# slimwatch_rev01.net
KiCad netlist of a schematic drawn in EAGLE
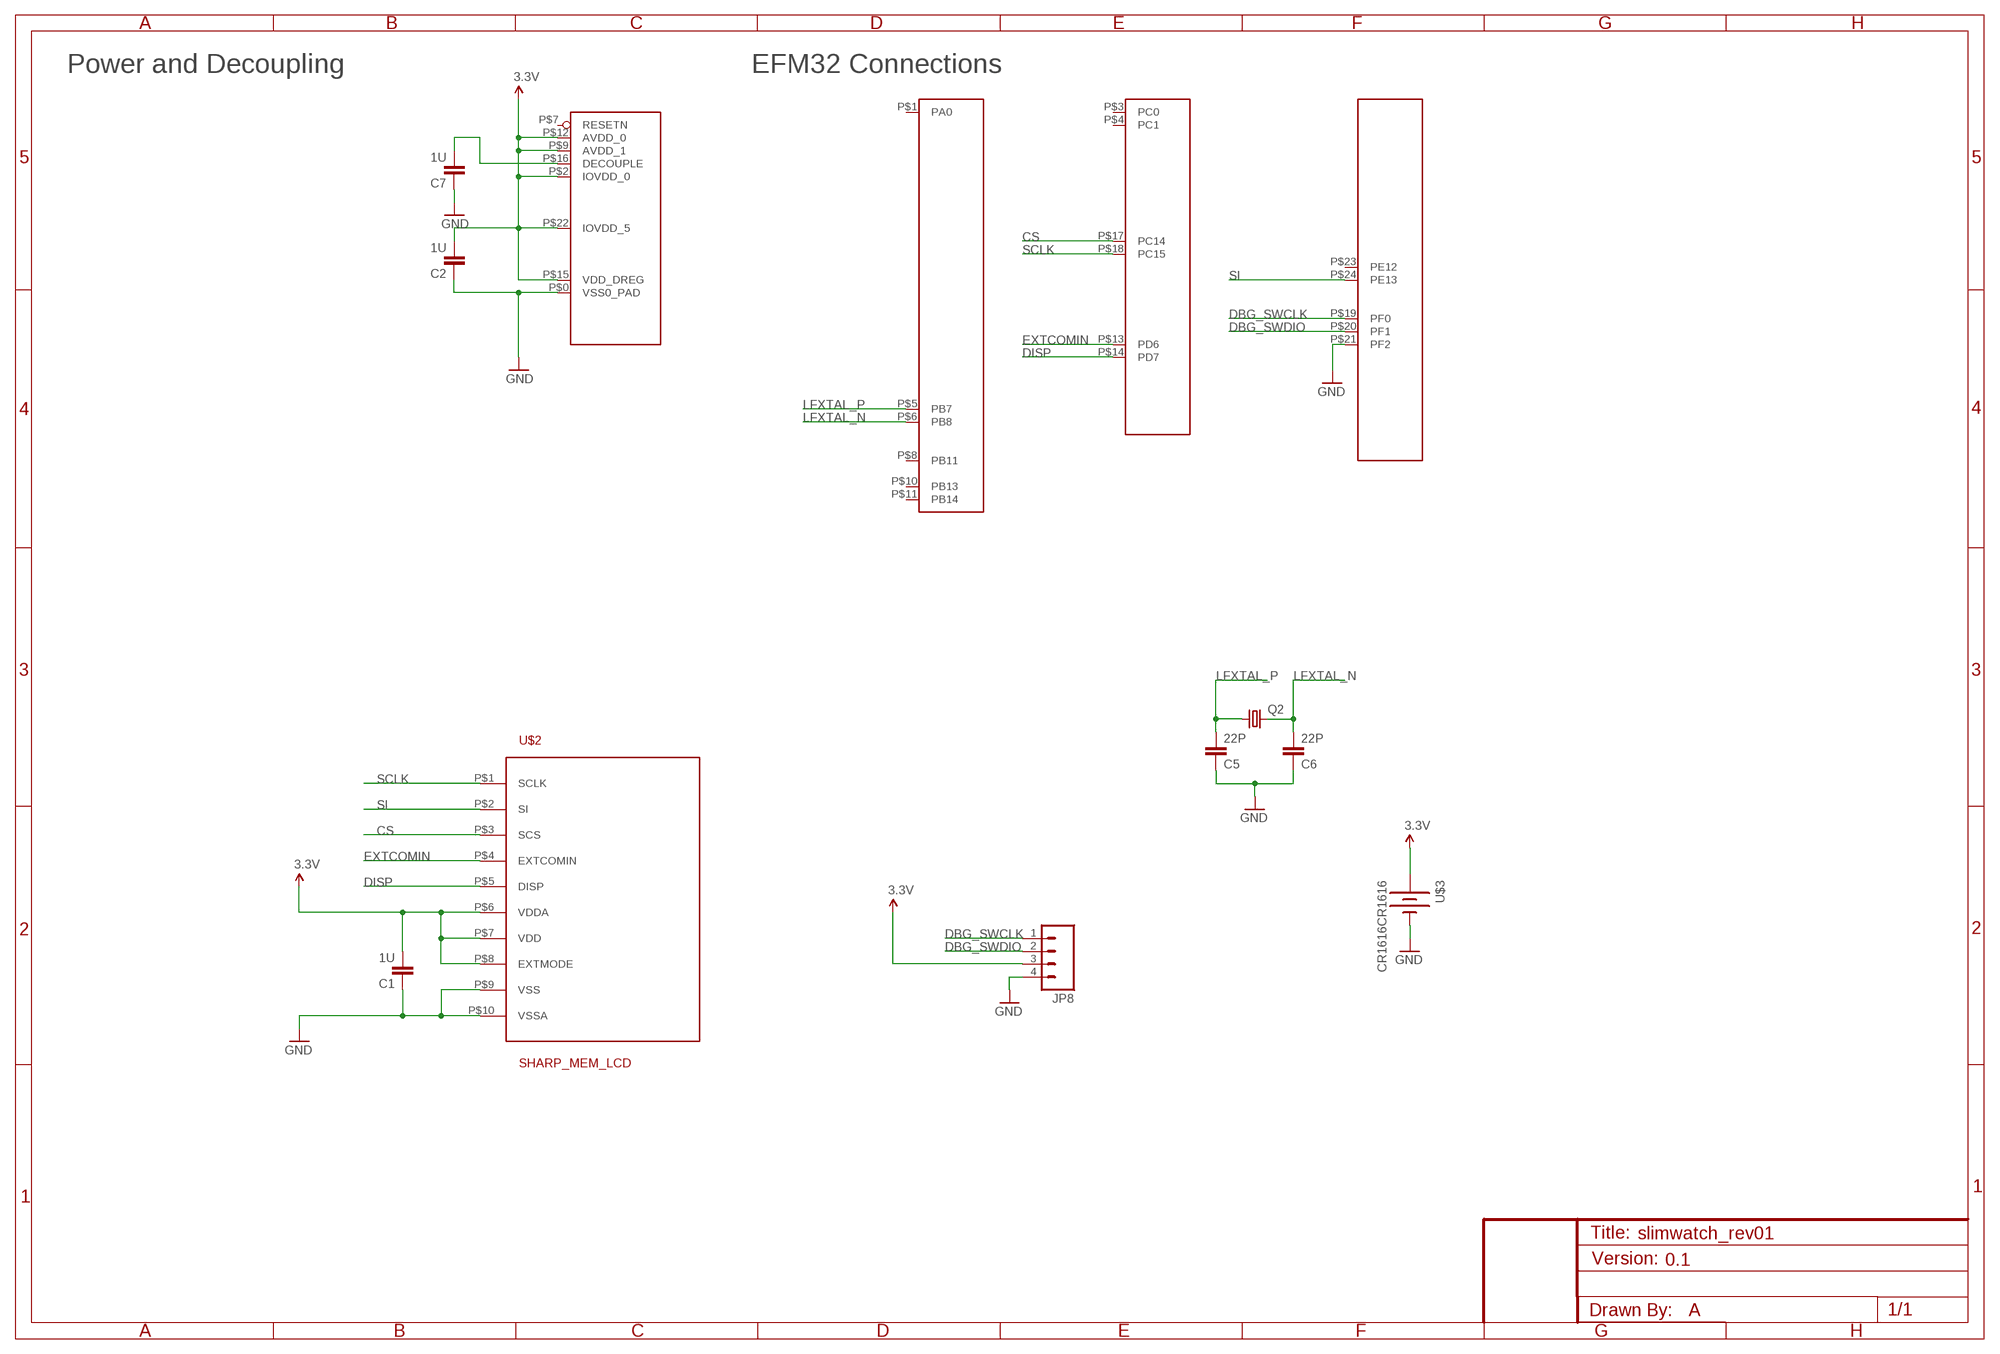
[diagram p0: schematic, sheet 1]

(export (version "E")
  (design (tool "Eeschema 10.0.6"))
  (components
    (comp (ref "C1")
      (value "1U")
      (footprint "eagle-import:C0603")
      (libsource (lib "eagle-import") (part "C-EUC0603"))
    )
    (comp (ref "C2")
      (value "1U")
      (footprint "eagle-import:C0603")
      (libsource (lib "eagle-import") (part "C-EUC0603"))
    )
    (comp (ref "C5")
      (value "22P")
      (footprint "eagle-import:C0603")
      (libsource (lib "eagle-import") (part "C-EUC0603"))
    )
    (comp (ref "C6")
      (value "22P")
      (footprint "eagle-import:C0603")
      (libsource (lib "eagle-import") (part "C-EUC0603"))
    )
    (comp (ref "C7")
      (value "1U")
      (footprint "eagle-import:C0603")
      (libsource (lib "eagle-import") (part "C-EUC0603"))
    )
    (comp (ref "JP8")
      (value "M04LOCK")
      (footprint "eagle-import:1X04_LOCK")
      (libsource (lib "eagle-import") (part "M04LOCK"))
    )
    (comp (ref "Q2")
      (value "CRYSTAL")
      (footprint "eagle-import:ABRACON_32KHZ_CRYSTAL")
      (libsource (lib "eagle-import") (part "CRYSTAL"))
    )
    (comp (ref "U$1")
      (value "EFM32GG980")
      (footprint "eagle-import:QFN24")
      (libsource (lib "eagle-import") (part "EFM32GG980"))
    )
    (comp (ref "U$2")
      (value "SHARP_MEM_LCD")
      (footprint "eagle-import:SHARP_MEM_LCD")
      (libsource (lib "eagle-import") (part "SHARP_MEM_LCD"))
    )
    (comp (ref "U$3")
      (value "CR1616CR1616")
      (footprint "eagle-import:BATTCON_16MM")
      (libsource (lib "eagle-import") (part "CR1616CR1616"))
    )
  )
  (nets
    (net (code "1") (name "/CS") (class "Default")
      (node (ref "U$1") (pin "P$17") (pinfunction "PC14_P$17") (pintype "bidirectional"))
      (node (ref "U$2") (pin "P$3") (pinfunction "SCS_P$3") (pintype "bidirectional"))
    )
    (net (code "2") (name "/DBG_SWCLK") (class "Default")
      (node (ref "JP8") (pin "1") (pinfunction "1_1") (pintype "passive"))
      (node (ref "U$1") (pin "P$19") (pinfunction "PF0_P$19") (pintype "bidirectional"))
    )
    (net (code "3") (name "/DBG_SWDIO") (class "Default")
      (node (ref "JP8") (pin "2") (pinfunction "2_2") (pintype "passive"))
      (node (ref "U$1") (pin "P$20") (pinfunction "PF1_P$20") (pintype "bidirectional"))
    )
    (net (code "4") (name "/DISP") (class "Default")
      (node (ref "U$1") (pin "P$14") (pinfunction "PD7_P$14") (pintype "bidirectional"))
      (node (ref "U$2") (pin "P$5") (pinfunction "DISP_P$5") (pintype "bidirectional"))
    )
    (net (code "5") (name "/EXTCOMIN") (class "Default")
      (node (ref "U$1") (pin "P$13") (pinfunction "PD6_P$13") (pintype "bidirectional"))
      (node (ref "U$2") (pin "P$4") (pinfunction "EXTCOMIN_P$4") (pintype "bidirectional"))
    )
    (net (code "6") (name "/LFXTAL_N") (class "Default")
      (node (ref "C6") (pin "2") (pinfunction "2_2") (pintype "passive"))
      (node (ref "Q2") (pin "P$2") (pinfunction "2_P$2") (pintype "passive"))
      (node (ref "U$1") (pin "P$6") (pinfunction "PB8_P$6") (pintype "bidirectional"))
    )
    (net (code "7") (name "/LFXTAL_P") (class "Default")
      (node (ref "C5") (pin "2") (pinfunction "2_2") (pintype "passive"))
      (node (ref "Q2") (pin "P$1") (pinfunction "1_P$1") (pintype "passive"))
      (node (ref "U$1") (pin "P$5") (pinfunction "PB7_P$5") (pintype "bidirectional"))
    )
    (net (code "8") (name "/SCLK") (class "Default")
      (node (ref "U$1") (pin "P$18") (pinfunction "PC15_P$18") (pintype "bidirectional"))
      (node (ref "U$2") (pin "P$1") (pinfunction "SCLK_P$1") (pintype "bidirectional"))
    )
    (net (code "9") (name "/SI") (class "Default")
      (node (ref "U$1") (pin "P$24") (pinfunction "PE13_P$24") (pintype "bidirectional"))
      (node (ref "U$2") (pin "P$2") (pinfunction "SI_P$2") (pintype "bidirectional"))
    )
    (net (code "10") (name "3.3V") (class "Default")
      (node (ref "C1") (pin "2") (pinfunction "2_2") (pintype "passive"))
      (node (ref "C2") (pin "2") (pinfunction "2_2") (pintype "passive"))
      (node (ref "JP8") (pin "3") (pinfunction "3_3") (pintype "passive"))
      (node (ref "U$1") (pin "P$12") (pinfunction "AVDD_0_P$12") (pintype "power_in"))
      (node (ref "U$1") (pin "P$15") (pinfunction "VDD_DREG_P$15") (pintype "power_in"))
      (node (ref "U$1") (pin "P$2") (pinfunction "IOVDD_0_P$2") (pintype "power_in"))
      (node (ref "U$1") (pin "P$22") (pinfunction "IOVDD_5_P$22") (pintype "power_in"))
      (node (ref "U$1") (pin "P$9") (pinfunction "AVDD_1_P$9") (pintype "power_in"))
      (node (ref "U$2") (pin "P$6") (pinfunction "VDDA_P$6") (pintype "bidirectional"))
      (node (ref "U$2") (pin "P$7") (pinfunction "VDD_P$7") (pintype "bidirectional"))
      (node (ref "U$2") (pin "P$8") (pinfunction "EXTMODE_P$8") (pintype "bidirectional"))
      (node (ref "U$3") (pin "P$2") (pinfunction "+_P$2") (pintype "power_in"))
      (node (ref "U$3") (pin "P$3") (pinfunction "+_P$3") (pintype "power_in"))
    )
    (net (code "11") (name "GND") (class "Default")
      (node (ref "C1") (pin "1") (pinfunction "1_1") (pintype "passive"))
      (node (ref "C2") (pin "1") (pinfunction "1_1") (pintype "passive"))
      (node (ref "C5") (pin "1") (pinfunction "1_1") (pintype "passive"))
      (node (ref "C6") (pin "1") (pinfunction "1_1") (pintype "passive"))
      (node (ref "C7") (pin "1") (pinfunction "1_1") (pintype "passive"))
      (node (ref "JP8") (pin "4") (pinfunction "4_4") (pintype "passive"))
      (node (ref "U$1") (pin "P$0") (pinfunction "VSS0_PAD_P$0") (pintype "power_in"))
      (node (ref "U$1") (pin "P$21") (pinfunction "PF2_P$21") (pintype "bidirectional"))
      (node (ref "U$2") (pin "P$10") (pinfunction "VSSA_P$10") (pintype "bidirectional"))
      (node (ref "U$2") (pin "P$9") (pinfunction "VSS_P$9") (pintype "bidirectional"))
      (node (ref "U$3") (pin "P$1") (pinfunction "-_P$1") (pintype "power_in"))
    )
    (net (code "12") (name "Net-(U$1D-DECOUPLE)") (class "Default")
      (node (ref "C7") (pin "2") (pinfunction "2_2") (pintype "passive"))
      (node (ref "U$1") (pin "P$16") (pinfunction "DECOUPLE_P$16") (pintype "power_in"))
    )
    (net (code "13") (name "unconnected-(U$1A-PA0-PadP$1)") (class "Default")
      (node (ref "U$1") (pin "P$1") (pinfunction "PA0_P$1") (pintype "bidirectional"))
    )
    (net (code "14") (name "unconnected-(U$1A-PB11-PadP$8)") (class "Default")
      (node (ref "U$1") (pin "P$8") (pinfunction "PB11_P$8") (pintype "bidirectional"))
    )
    (net (code "15") (name "unconnected-(U$1A-PB13-PadP$10)") (class "Default")
      (node (ref "U$1") (pin "P$10") (pinfunction "PB13_P$10") (pintype "bidirectional"))
    )
    (net (code "16") (name "unconnected-(U$1A-PB14-PadP$11)") (class "Default")
      (node (ref "U$1") (pin "P$11") (pinfunction "PB14_P$11") (pintype "bidirectional"))
    )
    (net (code "17") (name "unconnected-(U$1B-PC0-PadP$3)") (class "Default")
      (node (ref "U$1") (pin "P$3") (pinfunction "PC0_P$3") (pintype "bidirectional"))
    )
    (net (code "18") (name "unconnected-(U$1B-PC1-PadP$4)") (class "Default")
      (node (ref "U$1") (pin "P$4") (pinfunction "PC1_P$4") (pintype "bidirectional"))
    )
    (net (code "19") (name "unconnected-(U$1C-PE12-PadP$23)") (class "Default")
      (node (ref "U$1") (pin "P$23") (pinfunction "PE12_P$23") (pintype "bidirectional"))
    )
    (net (code "20") (name "unconnected-(U$1D-RESETN-PadP$7)") (class "Default")
      (node (ref "U$1") (pin "P$7") (pinfunction "RESETN_P$7") (pintype "bidirectional"))
    )
  )
)
